# 06_Output.net
KiCad netlist of a schematic drawn in Altium Designer
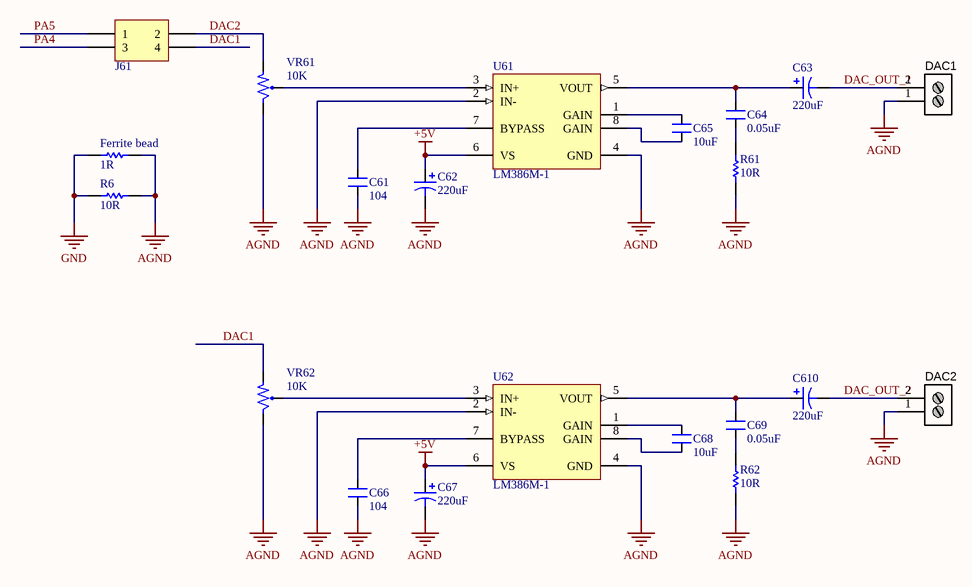
[diagram p0: [06] Output.SchDoc]

(export (version "E")
  (design (tool "Eeschema 10.0.6"))
  (components
    (comp (ref "C61")
      (value "104")
      (footprint "CAPC1608N")
      (fields (field (name "Comment") "CAP NP"))
      (libsource (lib "Tuan") (part "CAP NP"))
    )
    (comp (ref "C62")
      (value "220uF")
      (footprint "CAP 3.8mm")
      (fields (field (name "Comment") "Cap"))
      (libsource (lib "Tuan") (part "Cap"))
    )
    (comp (ref "C63")
      (value "220uF")
      (footprint "CAP 3.8mm")
      (fields (field (name "Comment") "Cap"))
      (libsource (lib "Tuan") (part "Cap"))
    )
    (comp (ref "C64")
      (value "0.05uF")
      (footprint "CAPC2012N_F")
      (fields (field (name "Comment") "CAP NP"))
      (libsource (lib "Tuan") (part "CAP NP"))
    )
    (comp (ref "C65")
      (value "10uF")
      (footprint "CAPC2012N_F")
      (fields (field (name "Comment") "CAP NP"))
      (libsource (lib "Tuan") (part "CAP NP"))
    )
    (comp (ref "C66")
      (value "104")
      (footprint "CAPC1608N")
      (fields (field (name "Comment") "CAP NP"))
      (libsource (lib "Tuan") (part "CAP NP"))
    )
    (comp (ref "C67")
      (value "220uF")
      (footprint "CAP 3.8mm")
      (fields (field (name "Comment") "Cap"))
      (libsource (lib "Tuan") (part "Cap"))
    )
    (comp (ref "C68")
      (value "10uF")
      (footprint "CAPC2012N_F")
      (fields (field (name "Comment") "CAP NP"))
      (libsource (lib "Tuan") (part "CAP NP"))
    )
    (comp (ref "C69")
      (value "0.05uF")
      (footprint "CAPC2012N_F")
      (fields (field (name "Comment") "CAP NP"))
      (libsource (lib "Tuan") (part "CAP NP"))
    )
    (comp (ref "C610")
      (value "220uF")
      (footprint "CAP 3.8mm")
      (fields (field (name "Comment") "Cap"))
      (libsource (lib "Tuan") (part "Cap"))
    )
    (comp (ref "DAC1")
      (value "Stackable ScrewTerm")
      (footprint "2P_PCB_ScrewTerm_200mil")
      (description "Terminal Block Screw Type THT 2-Position 3.81mm pitch")
      (libsource (lib "PBL - Connectors") (part "2P_ScrewTerm_90S_3.81MM"))
    )
    (comp (ref "DAC2")
      (value "Stackable ScrewTerm")
      (footprint "2P_PCB_ScrewTerm_200mil")
      (description "Terminal Block Screw Type THT 2-Position 3.81mm pitch")
      (libsource (lib "PBL - Connectors") (part "2P_ScrewTerm_90S_3.81MM"))
    )
    (comp (ref "Ferrite bead")
      (value "1R")
      (footprint "RESTH_0.0R_AXIAL-0.6")
      (fields (field (name "Comment") "Res"))
      (libsource (lib "Tuan") (part "Res"))
    )
    (comp (ref "J61")
      (value "Header 2X2")
      (footprint "heromap:HDR2X2")
      (description "Header, 2-Pin, Dual row")
      (fields (field (name "PUBLISHER") "Altium Limited"))
      (libsource (lib "heromap") (part "Header 2X2"))
    )
    (comp (ref "R6")
      (value "10R")
      (footprint "RESTH_0.0R_AXIAL-0.6")
      (fields (field (name "Comment") "Res"))
      (libsource (lib "Tuan") (part "Res"))
    )
    (comp (ref "R61")
      (value "10R")
      (footprint "RESC2012N_F")
      (fields (field (name "Comment") "Res"))
      (libsource (lib "Tuan") (part "Res"))
    )
    (comp (ref "R62")
      (value "10R")
      (footprint "RESC2012N_F")
      (fields (field (name "Comment") "Res"))
      (libsource (lib "Tuan") (part "Res"))
    )
    (comp (ref "U61")
      (value "LM386M-1")
      (footprint "M08A_N")
      (description "Low Voltage Audio Power Amplifier")
      (fields
        (field (name "MANUFACTURER") "National Semiconductor")
        (field (name "DIGIKEYPARTNUMBER") "LM386M-1-ND")
        (field (name "PUBLISHER") "Altium Limited")
      )
      (libsource (lib "NSC Audio") (part "LM386M-1"))
    )
    (comp (ref "U62")
      (value "LM386M-1")
      (footprint "M08A_N")
      (description "Low Voltage Audio Power Amplifier")
      (fields
        (field (name "MANUFACTURER") "National Semiconductor")
        (field (name "DIGIKEYPARTNUMBER") "LM386M-1-ND")
        (field (name "PUBLISHER") "Altium Limited")
      )
      (libsource (lib "NSC Audio") (part "LM386M-1"))
    )
    (comp (ref "VR61")
      (value "10K")
      (footprint "VR1")
      (description "Var Resistor")
      (libsource (lib "syhaunguyen") (part "VR1"))
    )
    (comp (ref "VR62")
      (value "10K")
      (footprint "VR1")
      (description "Var Resistor")
      (libsource (lib "syhaunguyen") (part "VR1"))
    )
  )
  (nets
    (net (code "1") (name "+5V") (class "Default")
      (node (ref "C62") (pin "1") (pinfunction "1_1") (pintype "passive"))
      (node (ref "C67") (pin "1") (pinfunction "1_1") (pintype "passive"))
      (node (ref "U61") (pin "6") (pinfunction "VS_6") (pintype "power_in"))
      (node (ref "U62") (pin "6") (pinfunction "VS_6") (pintype "power_in"))
    )
    (net (code "2") (name "/DAC1") (class "Default")
      (node (ref "J61") (pin "4") (pinfunction "4_4") (pintype "passive"))
      (node (ref "VR62") (pin "1") (pinfunction "1_1") (pintype "passive"))
    )
    (net (code "3") (name "/DAC2") (class "Default")
      (node (ref "J61") (pin "2") (pinfunction "2_2") (pintype "passive"))
      (node (ref "VR61") (pin "1") (pinfunction "1_1") (pintype "passive"))
    )
    (net (code "4") (name "/DAC_OUT_1") (class "Default")
      (node (ref "C63") (pin "2") (pinfunction "2_2") (pintype "passive"))
      (node (ref "DAC1") (pin "2") (pinfunction "2_2") (pintype "passive"))
    )
    (net (code "5") (name "/DAC_OUT_2") (class "Default")
      (node (ref "C610") (pin "2") (pinfunction "2_2") (pintype "passive"))
      (node (ref "DAC2") (pin "2") (pinfunction "2_2") (pintype "passive"))
    )
    (net (code "6") (name "/PA4") (class "Default")
      (node (ref "J61") (pin "3") (pinfunction "3_3") (pintype "passive"))
    )
    (net (code "7") (name "/PA5") (class "Default")
      (node (ref "J61") (pin "1") (pinfunction "1_1") (pintype "passive"))
    )
    (net (code "8") (name "AGND") (class "Default")
      (node (ref "C61") (pin "1") (pinfunction "1_1") (pintype "passive"))
      (node (ref "C62") (pin "2") (pinfunction "2_2") (pintype "passive"))
      (node (ref "C66") (pin "1") (pinfunction "1_1") (pintype "passive"))
      (node (ref "C67") (pin "2") (pinfunction "2_2") (pintype "passive"))
      (node (ref "DAC1") (pin "1") (pinfunction "1_1") (pintype "passive"))
      (node (ref "DAC2") (pin "1") (pinfunction "1_1") (pintype "passive"))
      (node (ref "Ferrite bead") (pin "2") (pinfunction "2_2") (pintype "passive"))
      (node (ref "R6") (pin "2") (pinfunction "2_2") (pintype "passive"))
      (node (ref "R61") (pin "1") (pinfunction "1_1") (pintype "passive"))
      (node (ref "R62") (pin "1") (pinfunction "1_1") (pintype "passive"))
      (node (ref "U61") (pin "2") (pinfunction "IN-_2") (pintype "input"))
      (node (ref "U61") (pin "4") (pinfunction "GND_4") (pintype "power_in"))
      (node (ref "U62") (pin "2") (pinfunction "IN-_2") (pintype "input"))
      (node (ref "U62") (pin "4") (pinfunction "GND_4") (pintype "power_in"))
      (node (ref "VR61") (pin "3") (pinfunction "3_3") (pintype "passive"))
      (node (ref "VR62") (pin "3") (pinfunction "3_3") (pintype "passive"))
    )
    (net (code "9") (name "GND") (class "Default")
      (node (ref "Ferrite bead") (pin "1") (pinfunction "1_1") (pintype "passive"))
      (node (ref "R6") (pin "1") (pinfunction "1_1") (pintype "passive"))
    )
    (net (code "10") (name "Net-(C64-Pad2)") (class "Default")
      (node (ref "C64") (pin "2") (pinfunction "2_2") (pintype "passive"))
      (node (ref "R61") (pin "2") (pinfunction "2_2") (pintype "passive"))
    )
    (net (code "11") (name "Net-(C65-Pad1)") (class "Default")
      (node (ref "C65") (pin "1") (pinfunction "1_1") (pintype "passive"))
      (node (ref "U61") (pin "8") (pinfunction "GAIN_8") (pintype "passive"))
    )
    (net (code "12") (name "Net-(C65-Pad2)") (class "Default")
      (node (ref "C65") (pin "2") (pinfunction "2_2") (pintype "passive"))
      (node (ref "U61") (pin "1") (pinfunction "GAIN_1") (pintype "passive"))
    )
    (net (code "13") (name "Net-(C68-Pad1)") (class "Default")
      (node (ref "C68") (pin "1") (pinfunction "1_1") (pintype "passive"))
      (node (ref "U62") (pin "8") (pinfunction "GAIN_8") (pintype "passive"))
    )
    (net (code "14") (name "Net-(C68-Pad2)") (class "Default")
      (node (ref "C68") (pin "2") (pinfunction "2_2") (pintype "passive"))
      (node (ref "U62") (pin "1") (pinfunction "GAIN_1") (pintype "passive"))
    )
    (net (code "15") (name "Net-(C69-Pad2)") (class "Default")
      (node (ref "C69") (pin "2") (pinfunction "2_2") (pintype "passive"))
      (node (ref "R62") (pin "2") (pinfunction "2_2") (pintype "passive"))
    )
    (net (code "16") (name "Net-(U61-BYPASS)") (class "Default")
      (node (ref "C61") (pin "2") (pinfunction "2_2") (pintype "passive"))
      (node (ref "U61") (pin "7") (pinfunction "BYPASS_7") (pintype "passive"))
    )
    (net (code "17") (name "Net-(U61-IN+)") (class "Default")
      (node (ref "U61") (pin "3") (pinfunction "IN+_3") (pintype "input"))
      (node (ref "VR61") (pin "2") (pinfunction "2_2") (pintype "passive"))
    )
    (net (code "18") (name "Net-(U61-VOUT)") (class "Default")
      (node (ref "C63") (pin "1") (pinfunction "1_1") (pintype "passive"))
      (node (ref "C64") (pin "1") (pinfunction "1_1") (pintype "passive"))
      (node (ref "U61") (pin "5") (pinfunction "VOUT_5") (pintype "output"))
    )
    (net (code "19") (name "Net-(U62-BYPASS)") (class "Default")
      (node (ref "C66") (pin "2") (pinfunction "2_2") (pintype "passive"))
      (node (ref "U62") (pin "7") (pinfunction "BYPASS_7") (pintype "passive"))
    )
    (net (code "20") (name "Net-(U62-IN+)") (class "Default")
      (node (ref "U62") (pin "3") (pinfunction "IN+_3") (pintype "input"))
      (node (ref "VR62") (pin "2") (pinfunction "2_2") (pintype "passive"))
    )
    (net (code "21") (name "Net-(U62-VOUT)") (class "Default")
      (node (ref "C610") (pin "1") (pinfunction "1_1") (pintype "passive"))
      (node (ref "C69") (pin "1") (pinfunction "1_1") (pintype "passive"))
      (node (ref "U62") (pin "5") (pinfunction "VOUT_5") (pintype "output"))
    )
  )
)
